# 9_-STM32F407_Controller.net
KiCad netlist of a schematic drawn in Altium Designer
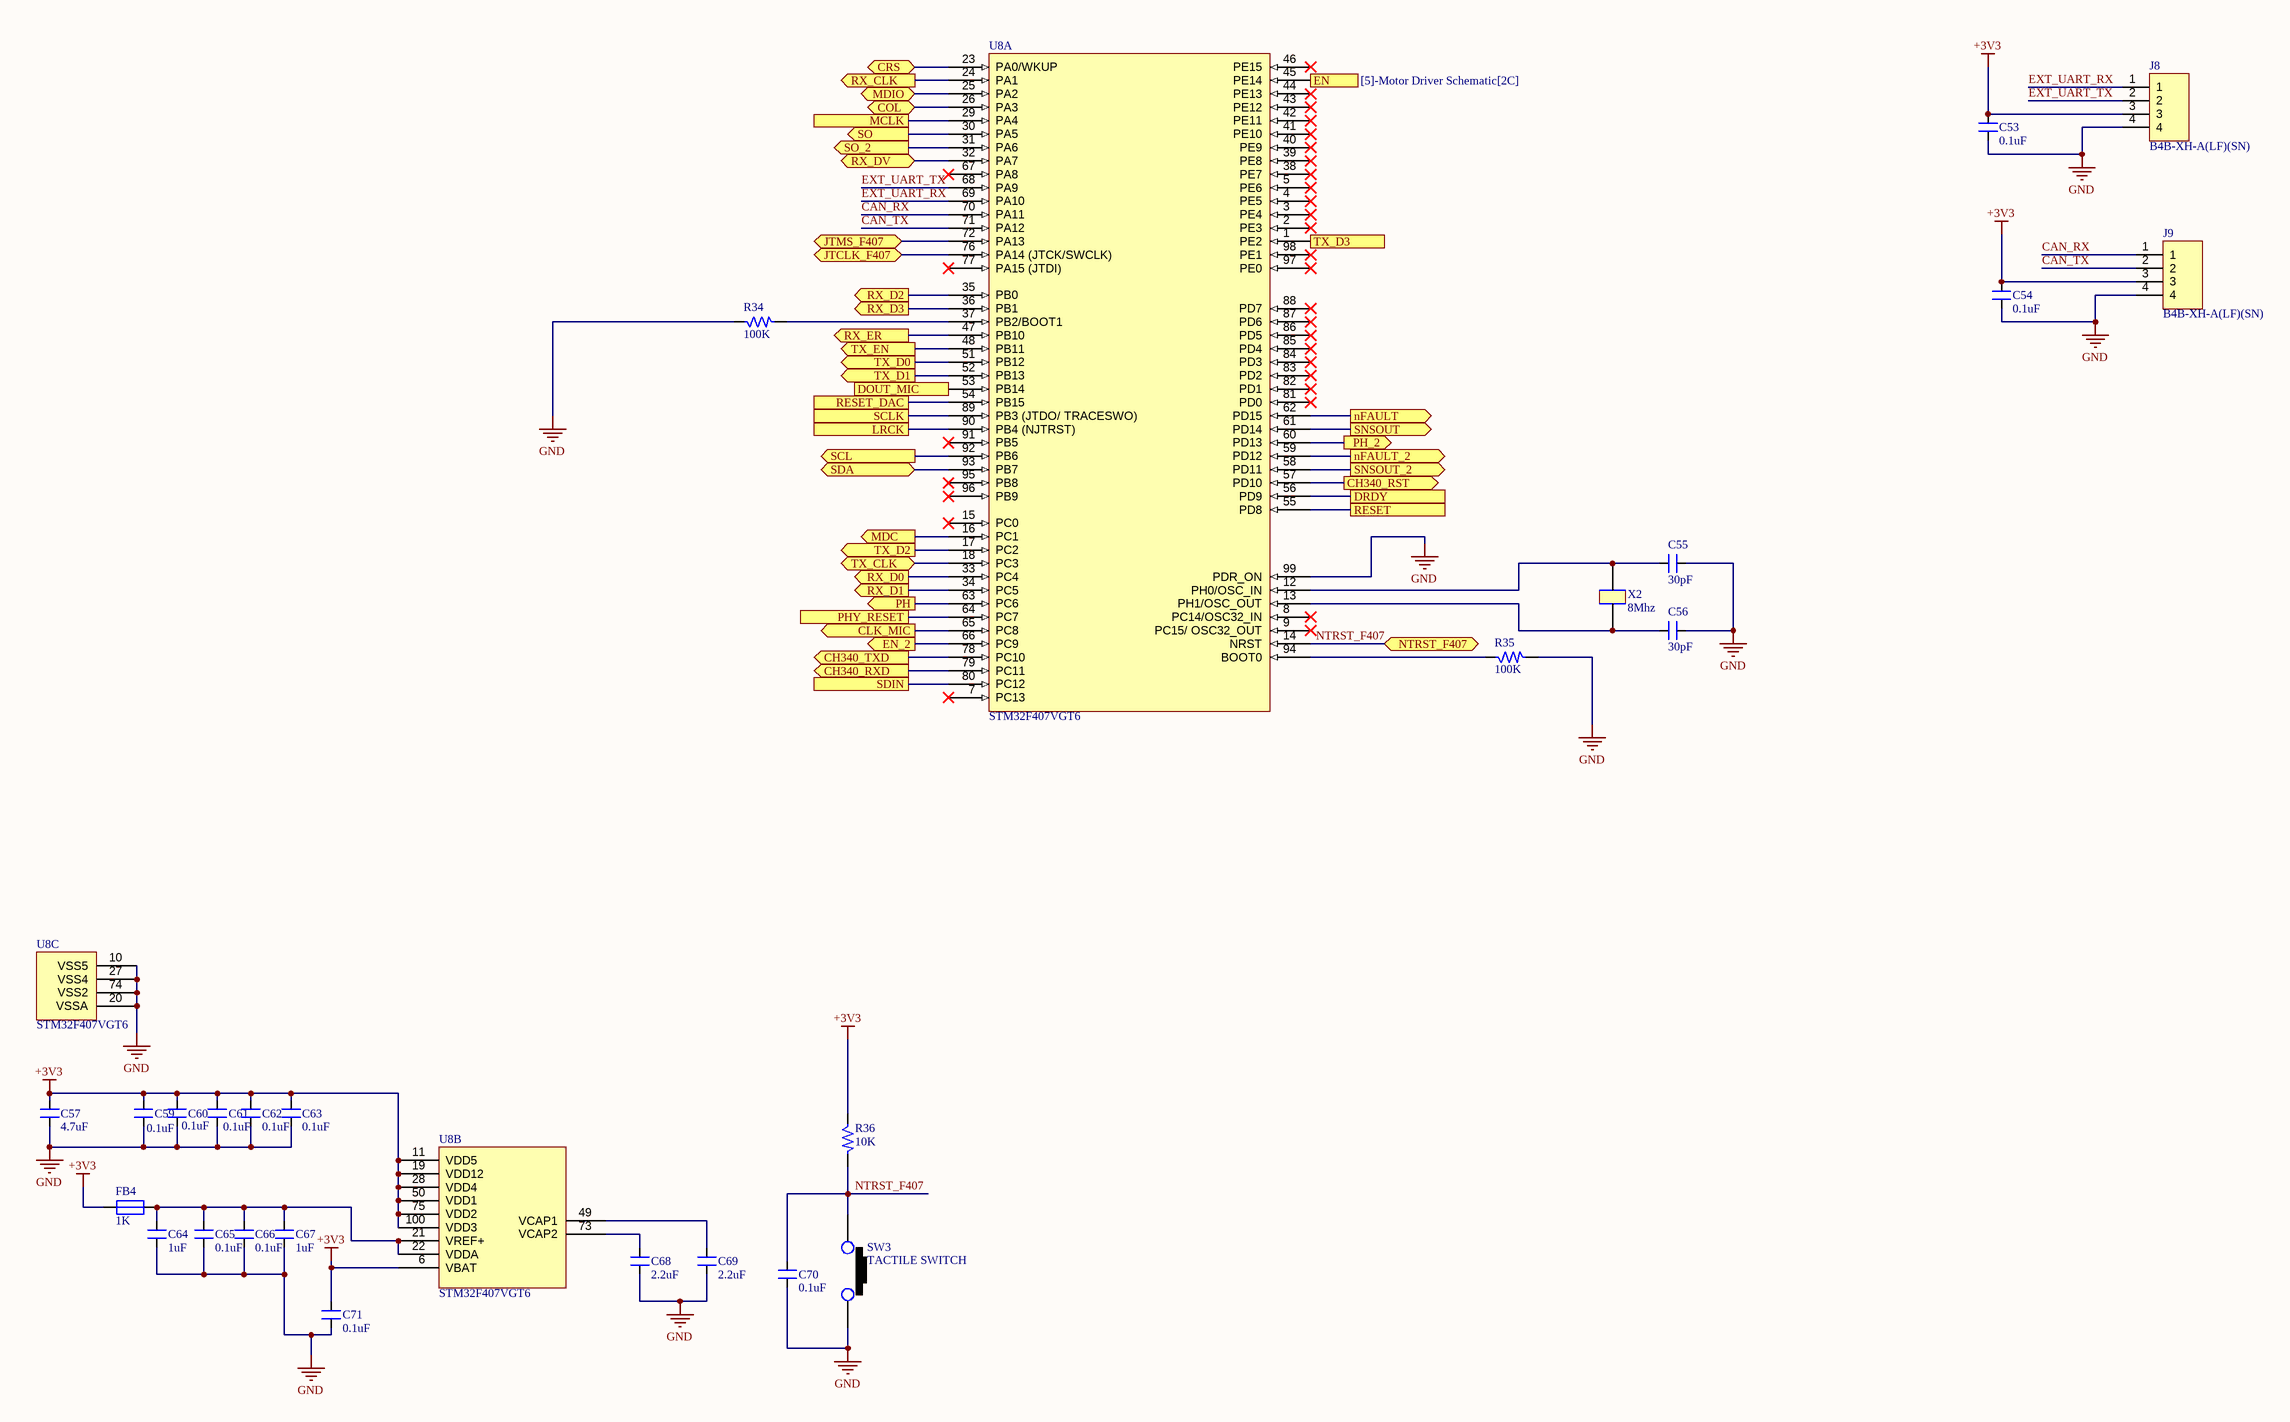
[diagram p0: [9]-STM32F407 Controller.SchDoc]

(export (version "E")
  (design (tool "Eeschema 10.0.6"))
  (components
    (comp (ref "C53")
      (value "0.1uF")
      (footprint "CAP_0805")
      (description "0.1µF ±10% 50V Ceramic Capacitor X7R 0805 (2012 Metric)")
      (fields
        (field (name "MANUFACTURER") "Samsung")
        (field (name "MANUFACTURER PART NUMBER") "CL21B104KBCNNNC")
      )
      (libsource (lib "ESTEEMPCBLIB") (part "CAP_0.1uF-50V-10%-0805"))
    )
    (comp (ref "C54")
      (value "0.1uF")
      (footprint "CAP_0805")
      (description "0.1µF ±10% 50V Ceramic Capacitor X7R 0805 (2012 Metric)")
      (fields
        (field (name "MANUFACTURER") "Samsung")
        (field (name "MANUFACTURER PART NUMBER") "CL21B104KBCNNNC")
      )
      (libsource (lib "ESTEEMPCBLIB") (part "CAP_0.1uF-50V-10%-0805"))
    )
    (comp (ref "C55")
      (value "30pF")
      (footprint "CAP_0805")
      (description "±10% 50V Ceramic Capacitor C0G, NP0 0805 (2012 Metric)")
      (fields
        (field (name "MANUFACTURER PART NUMBER") "C0805C300K5GAC7800")
        (field (name "MANUFACTURER") "KEMET")
      )
      (libsource (lib "ESTEEMPCBLIB") (part "CAP_30pF-50V-10%-0805"))
    )
    (comp (ref "C56")
      (value "30pF")
      (footprint "CAP_0805")
      (description "±10% 50V Ceramic Capacitor C0G, NP0 0805 (2012 Metric)")
      (fields
        (field (name "MANUFACTURER PART NUMBER") "C0805C300K5GAC7800")
        (field (name "MANUFACTURER") "KEMET")
      )
      (libsource (lib "ESTEEMPCBLIB") (part "CAP_30pF-50V-10%-0805"))
    )
    (comp (ref "C57")
      (value "4.7uF")
      (footprint "CAP_0805")
      (description "4.7µF ±10% 50V Ceramic Capacitor X5R 0805 (2012 Metric)")
      (fields
        (field (name "MANUFACTURER") "Yageo")
        (field (name "MANUFACTURER PART NUMBER") "GRM21BR61H475KE51L")
      )
      (libsource (lib "ESTEEMPCBLIB") (part "CAP_4.7uF-50V-10%-0805"))
    )
    (comp (ref "C59")
      (value "0.1uF")
      (footprint "CAP_0805")
      (description "0.1µF ±10% 50V Ceramic Capacitor X7R 0805 (2012 Metric)")
      (fields
        (field (name "MANUFACTURER") "Samsung")
        (field (name "MANUFACTURER PART NUMBER") "CL21B104KBCNNNC")
      )
      (libsource (lib "ESTEEMPCBLIB") (part "CAP_0.1uF-50V-10%-0805"))
    )
    (comp (ref "C60")
      (value "0.1uF")
      (footprint "CAP_0805")
      (description "0.1µF ±10% 50V Ceramic Capacitor X7R 0805 (2012 Metric)")
      (fields
        (field (name "MANUFACTURER") "Samsung")
        (field (name "MANUFACTURER PART NUMBER") "CL21B104KBCNNNC")
      )
      (libsource (lib "ESTEEMPCBLIB") (part "CAP_0.1uF-50V-10%-0805"))
    )
    (comp (ref "C61")
      (value "0.1uF")
      (footprint "CAP_0805")
      (description "0.1µF ±10% 50V Ceramic Capacitor X7R 0805 (2012 Metric)")
      (fields
        (field (name "MANUFACTURER") "Samsung")
        (field (name "MANUFACTURER PART NUMBER") "CL21B104KBCNNNC")
      )
      (libsource (lib "ESTEEMPCBLIB") (part "CAP_0.1uF-50V-10%-0805"))
    )
    (comp (ref "C62")
      (value "0.1uF")
      (footprint "CAP_0805")
      (description "0.1µF ±10% 50V Ceramic Capacitor X7R 0805 (2012 Metric)")
      (fields
        (field (name "MANUFACTURER") "Samsung")
        (field (name "MANUFACTURER PART NUMBER") "CL21B104KBCNNNC")
      )
      (libsource (lib "ESTEEMPCBLIB") (part "CAP_0.1uF-50V-10%-0805"))
    )
    (comp (ref "C63")
      (value "0.1uF")
      (footprint "CAP_0805")
      (description "0.1µF ±10% 50V Ceramic Capacitor X7R 0805 (2012 Metric)")
      (fields
        (field (name "MANUFACTURER") "Samsung")
        (field (name "MANUFACTURER PART NUMBER") "CL21B104KBCNNNC")
      )
      (libsource (lib "ESTEEMPCBLIB") (part "CAP_0.1uF-50V-10%-0805"))
    )
    (comp (ref "C64")
      (value "1uF")
      (footprint "CAP_0805")
      (description "1µF ±5% 50V Ceramic Capacitor X7R 0805 (2012 Metric)")
      (fields
        (field (name "MANUFACTURER") "Samsung")
        (field (name "MANUFACTURER PART NUMBER") "CC0805JKX7R9BB105")
      )
      (libsource (lib "ESTEEMPCBLIB") (part "CAP_1uF-50V-5%-0805"))
    )
    (comp (ref "C65")
      (value "0.1uF")
      (footprint "CAP_0805")
      (description "0.1µF ±10% 50V Ceramic Capacitor X7R 0805 (2012 Metric)")
      (fields
        (field (name "MANUFACTURER") "Samsung")
        (field (name "MANUFACTURER PART NUMBER") "CL21B104KBCNNNC")
      )
      (libsource (lib "ESTEEMPCBLIB") (part "CAP_0.1uF-50V-10%-0805"))
    )
    (comp (ref "C66")
      (value "0.1uF")
      (footprint "CAP_0805")
      (description "0.1µF ±10% 50V Ceramic Capacitor X7R 0805 (2012 Metric)")
      (fields
        (field (name "MANUFACTURER") "Samsung")
        (field (name "MANUFACTURER PART NUMBER") "CL21B104KBCNNNC")
      )
      (libsource (lib "ESTEEMPCBLIB") (part "CAP_0.1uF-50V-10%-0805"))
    )
    (comp (ref "C67")
      (value "1uF")
      (footprint "CAP_0805")
      (description "1µF ±5% 50V Ceramic Capacitor X7R 0805 (2012 Metric)")
      (fields
        (field (name "MANUFACTURER") "Samsung")
        (field (name "MANUFACTURER PART NUMBER") "CC0805JKX7R9BB105")
      )
      (libsource (lib "ESTEEMPCBLIB") (part "CAP_1uF-50V-5%-0805"))
    )
    (comp (ref "C68")
      (value "2.2uF")
      (footprint "CAP_0805")
      (description "2.2µF ±10% 25V Ceramic Capacitor X7R 0805 (2012 Metric)")
      (fields
        (field (name "MANUFACTURER") "KEMET")
        (field (name "MANUFACTURER PART NUMBER") "CL21B225KAFNFNE")
      )
      (libsource (lib "ESTEEMPCBLIB") (part "CAP_2.2uF-25V-10%-0805"))
    )
    (comp (ref "C69")
      (value "2.2uF")
      (footprint "CAP_0805")
      (description "2.2µF ±10% 25V Ceramic Capacitor X7R 0805 (2012 Metric)")
      (fields
        (field (name "MANUFACTURER") "KEMET")
        (field (name "MANUFACTURER PART NUMBER") "CL21B225KAFNFNE")
      )
      (libsource (lib "ESTEEMPCBLIB") (part "CAP_2.2uF-25V-10%-0805"))
    )
    (comp (ref "C70")
      (value "0.1uF")
      (footprint "CAP_0805")
      (description "0.1µF ±10% 50V Ceramic Capacitor X7R 0805 (2012 Metric)")
      (fields
        (field (name "MANUFACTURER") "Samsung")
        (field (name "MANUFACTURER PART NUMBER") "CL21B104KBCNNNC")
      )
      (libsource (lib "ESTEEMPCBLIB") (part "CAP_0.1uF-50V-10%-0805"))
    )
    (comp (ref "C71")
      (value "0.1uF")
      (footprint "CAP_0805")
      (description "0.1µF ±10% 50V Ceramic Capacitor X7R 0805 (2012 Metric)")
      (fields
        (field (name "MANUFACTURER") "Samsung")
        (field (name "MANUFACTURER PART NUMBER") "CL21B104KBCNNNC")
      )
      (libsource (lib "ESTEEMPCBLIB") (part "CAP_0.1uF-50V-10%-0805"))
    )
    (comp (ref "FB4")
      (value "1K")
      (footprint "IND_0805")
      (description "1 kOhms @ 100MHz 1 Power Line Ferrite Bead 0805 (2012 Metric) 1.6A")
      (fields
        (field (name "MANUFACTURER") "Laird")
        (field (name "MANUFACTURER PART NUMBER") "BLM21SP102SH1D")
      )
      (libsource (lib "ESTEEMPCBLIB") (part "FB_1K-100MHZ-1.6A-0805"))
    )
    (comp (ref "J8")
      (value "B4B-XH-A(LF)(SN)")
      (footprint "CON4_100_B4B-XH-A_TH_ST")
      (description "4 Pins, 1 Row 2.54mm Pitch, straight Connector, male")
      (fields (field (name "MANUFACTURER") "Wurth Electronics") (field (name "MATING PART NUMBER") "XHP-4"))
      (libsource (lib "ESTEEMPCBLIB") (part "CON-PLG_4X1-100-ST-TH"))
    )
    (comp (ref "J9")
      (value "B4B-XH-A(LF)(SN)")
      (footprint "CON4_100_B4B-XH-A_TH_ST")
      (description "4 Pins, 1 Row 2.54mm Pitch, straight Connector, male")
      (fields (field (name "MANUFACTURER") "Wurth Electronics") (field (name "MATING PART NUMBER") "XHP-4"))
      (libsource (lib "ESTEEMPCBLIB") (part "CON-PLG_4X1-100-ST-TH"))
    )
    (comp (ref "R34")
      (value "100K")
      (footprint "RES_0603")
      (description "100 kOhms ±1% 0.1W, 1/10W Chip Resistor 0603 (1608 Metric) Automotive AEC-Q200 Thick Film")
      (fields
        (field (name "MANUFACTURER") "Stackpole Electronics")
        (field (name "MANUFACTURER PART NUMBER") "RMCF0603FT100K")
      )
      (libsource (lib "ESTEEMPCBLIB") (part "RES_100K-0.1W-1%-0603"))
    )
    (comp (ref "R35")
      (value "100K")
      (footprint "RES_0603")
      (description "100 kOhms ±1% 0.1W, 1/10W Chip Resistor 0603 (1608 Metric) Automotive AEC-Q200 Thick Film")
      (fields
        (field (name "MANUFACTURER") "Stackpole Electronics")
        (field (name "MANUFACTURER PART NUMBER") "RMCF0603FT100K")
      )
      (libsource (lib "ESTEEMPCBLIB") (part "RES_100K-0.1W-1%-0603"))
    )
    (comp (ref "R36")
      (value "10K")
      (footprint "RES_0603")
      (description "10 kOhms ±1% 0.1W, 1/10W Chip Resistor 0603 (1608 Metric) Automotive AEC-Q200 Thick Film")
      (fields (field (name "MANUFACTURER") "Walsin") (field (name "MANUFACTURER PART NUMBER") "WR06X1002FTL"))
      (libsource (lib "ESTEEMPCBLIB") (part "RES_10K-0.1W-1%-0603"))
    )
    (comp (ref "SW3")
      (value "TACTILE SWITCH")
      (footprint "SW_342_SMD")
      (description "Tactile Switch SPST-NO Top Actuated Surface Mount")
      (fields
        (field (name "MANUFACTURER") "ITT C&K")
        (field (name "MANUFACTURER PART NUMBER") "RS-282G05A3-SMRT")
      )
      (libsource (lib "ESTEEMPCBLIB") (part "SW1_RS-282G05A3-SMRT-SMD"))
    )
    (comp (ref "U8")
      (value "STM32F407VGT6")
      (footprint "QFN100_19.6_669_58X10_SMD")
      (description "ARM® Cortex®-M4 STM32F4 Microcontroller IC 32-Bit 168MHz 1MB (1M x 8) FLASH 100-LQFP (14x14)")
      (fields (field (name "MANUFACTURER") "STMicroelectronics"))
      (libsource (lib "ESTEEMPCBLIB") (part "IC_STM32F407VGT6"))
    )
    (comp (ref "X2")
      (value "8Mhz")
      (footprint "XTAL_314_240X47_SMD")
      (description "8MHz ±30ppm Crystal 32pF 60 Ohms HC-49/US")
      (fields
        (field (name "MANUFACTURER") "Fox Electronics")
        (field (name "MANUFACTURER PART NUMBER") "ECS-80-32-5PX-TR")
      )
      (libsource (lib "ESTEEMPCBLIB") (part "XTAL_8MHZ-ECS-80-32-5PX-SMD"))
    )
  )
  (nets
    (net (code "1") (name "+3V3") (class "Default")
      (node (ref "C53") (pin "2") (pinfunction "2_2") (pintype "passive"))
      (node (ref "C54") (pin "2") (pinfunction "2_2") (pintype "passive"))
      (node (ref "C57") (pin "2") (pinfunction "2_2") (pintype "passive"))
      (node (ref "C59") (pin "2") (pinfunction "2_2") (pintype "passive"))
      (node (ref "C60") (pin "2") (pinfunction "2_2") (pintype "passive"))
      (node (ref "C61") (pin "2") (pinfunction "2_2") (pintype "passive"))
      (node (ref "C62") (pin "2") (pinfunction "2_2") (pintype "passive"))
      (node (ref "C63") (pin "2") (pinfunction "2_2") (pintype "passive"))
      (node (ref "C71") (pin "2") (pinfunction "2_2") (pintype "passive"))
      (node (ref "FB4") (pin "1") (pinfunction "1_1") (pintype "passive"))
      (node (ref "J8") (pin "3") (pinfunction "3_3") (pintype "passive"))
      (node (ref "J9") (pin "3") (pinfunction "3_3") (pintype "passive"))
      (node (ref "R36") (pin "1") (pinfunction "1_1") (pintype "passive"))
      (node (ref "U8") (pin "100") (pinfunction "VDD3_100") (pintype "passive"))
      (node (ref "U8") (pin "11") (pinfunction "VDD5_11") (pintype "passive"))
      (node (ref "U8") (pin "19") (pinfunction "VDD12_19") (pintype "passive"))
      (node (ref "U8") (pin "28") (pinfunction "VDD4_28") (pintype "passive"))
      (node (ref "U8") (pin "50") (pinfunction "VDD1_50") (pintype "passive"))
      (node (ref "U8") (pin "6") (pinfunction "VBAT_6") (pintype "passive"))
      (node (ref "U8") (pin "75") (pinfunction "VDD2_75") (pintype "passive"))
    )
    (net (code "2") (name "/CAN_RX") (class "Default")
      (node (ref "J9") (pin "1") (pinfunction "1_1") (pintype "passive"))
      (node (ref "U8") (pin "70") (pinfunction "PA11_70") (pintype "input"))
    )
    (net (code "3") (name "/CAN_TX") (class "Default")
      (node (ref "J9") (pin "2") (pinfunction "2_2") (pintype "passive"))
      (node (ref "U8") (pin "71") (pinfunction "PA12_71") (pintype "input"))
    )
    (net (code "4") (name "/CH340_RST") (class "Default")
      (node (ref "U8") (pin "57") (pinfunction "PD10_57") (pintype "input"))
    )
    (net (code "5") (name "/CH340_RXD") (class "Default")
      (node (ref "U8") (pin "79") (pinfunction "PC11_79") (pintype "input"))
    )
    (net (code "6") (name "/CH340_TXD") (class "Default")
      (node (ref "U8") (pin "78") (pinfunction "PC10_78") (pintype "input"))
    )
    (net (code "7") (name "/CLK_MIC") (class "Default")
      (node (ref "U8") (pin "65") (pinfunction "PC8_65") (pintype "input"))
    )
    (net (code "8") (name "/COL") (class "Default")
      (node (ref "U8") (pin "26") (pinfunction "PA3_26") (pintype "input"))
    )
    (net (code "9") (name "/CRS") (class "Default")
      (node (ref "U8") (pin "23") (pinfunction "PA0/WKUP_23") (pintype "input"))
    )
    (net (code "10") (name "/DOUT_MIC") (class "Default")
      (node (ref "U8") (pin "53") (pinfunction "PB14_53") (pintype "input"))
    )
    (net (code "11") (name "/DRDY") (class "Default")
      (node (ref "U8") (pin "56") (pinfunction "PD9_56") (pintype "input"))
    )
    (net (code "12") (name "/EN") (class "Default")
      (node (ref "U8") (pin "45") (pinfunction "PE14_45") (pintype "input"))
    )
    (net (code "13") (name "/EN_2") (class "Default")
      (node (ref "U8") (pin "66") (pinfunction "PC9_66") (pintype "input"))
    )
    (net (code "14") (name "/EXT_UART_RX") (class "Default")
      (node (ref "J8") (pin "1") (pinfunction "1_1") (pintype "passive"))
      (node (ref "U8") (pin "69") (pinfunction "PA10_69") (pintype "input"))
    )
    (net (code "15") (name "/EXT_UART_TX") (class "Default")
      (node (ref "J8") (pin "2") (pinfunction "2_2") (pintype "passive"))
      (node (ref "U8") (pin "68") (pinfunction "PA9_68") (pintype "input"))
    )
    (net (code "16") (name "/JTCLK_F407") (class "Default")
      (node (ref "U8") (pin "76") (pinfunction "PA14_(JTCK/SWCLK)_76") (pintype "input"))
    )
    (net (code "17") (name "/JTMS_F407") (class "Default")
      (node (ref "U8") (pin "72") (pinfunction "PA13_72") (pintype "input"))
    )
    (net (code "18") (name "/LRCK") (class "Default")
      (node (ref "U8") (pin "90") (pinfunction "PB4_(NJTRST)_90") (pintype "input"))
    )
    (net (code "19") (name "/MCLK") (class "Default")
      (node (ref "U8") (pin "29") (pinfunction "PA4_29") (pintype "input"))
    )
    (net (code "20") (name "/MDC") (class "Default")
      (node (ref "U8") (pin "16") (pinfunction "PC1_16") (pintype "input"))
    )
    (net (code "21") (name "/MDIO") (class "Default")
      (node (ref "U8") (pin "25") (pinfunction "PA2_25") (pintype "input"))
    )
    (net (code "22") (name "/NTRST_F407") (class "Default")
      (node (ref "C70") (pin "2") (pinfunction "2_2") (pintype "passive"))
      (node (ref "R36") (pin "2") (pinfunction "2_2") (pintype "passive"))
      (node (ref "SW3") (pin "1") (pinfunction "1_1") (pintype "passive"))
      (node (ref "U8") (pin "14") (pinfunction "NRST_14") (pintype "input"))
    )
    (net (code "23") (name "/PH") (class "Default")
      (node (ref "U8") (pin "63") (pinfunction "PC6_63") (pintype "input"))
    )
    (net (code "24") (name "/PHY_RESET") (class "Default")
      (node (ref "U8") (pin "64") (pinfunction "PC7_64") (pintype "input"))
    )
    (net (code "25") (name "/PH_2") (class "Default")
      (node (ref "U8") (pin "60") (pinfunction "PD13_60") (pintype "input"))
    )
    (net (code "26") (name "/RESET") (class "Default")
      (node (ref "U8") (pin "55") (pinfunction "PD8_55") (pintype "input"))
    )
    (net (code "27") (name "/RESET_DAC") (class "Default")
      (node (ref "U8") (pin "54") (pinfunction "PB15_54") (pintype "input"))
    )
    (net (code "28") (name "/RX_CLK") (class "Default")
      (node (ref "U8") (pin "24") (pinfunction "PA1_24") (pintype "input"))
    )
    (net (code "29") (name "/RX_D0") (class "Default")
      (node (ref "U8") (pin "33") (pinfunction "PC4_33") (pintype "input"))
    )
    (net (code "30") (name "/RX_D1") (class "Default")
      (node (ref "U8") (pin "34") (pinfunction "PC5_34") (pintype "input"))
    )
    (net (code "31") (name "/RX_D2") (class "Default")
      (node (ref "U8") (pin "35") (pinfunction "PB0_35") (pintype "input"))
    )
    (net (code "32") (name "/RX_D3") (class "Default")
      (node (ref "U8") (pin "36") (pinfunction "PB1_36") (pintype "input"))
    )
    (net (code "33") (name "/RX_DV") (class "Default")
      (node (ref "U8") (pin "32") (pinfunction "PA7_32") (pintype "input"))
    )
    (net (code "34") (name "/RX_ER") (class "Default")
      (node (ref "U8") (pin "47") (pinfunction "PB10_47") (pintype "input"))
    )
    (net (code "35") (name "/SCL") (class "Default")
      (node (ref "U8") (pin "92") (pinfunction "PB6_92") (pintype "input"))
    )
    (net (code "36") (name "/SCLK") (class "Default")
      (node (ref "U8") (pin "89") (pinfunction "PB3_(JTDO/_TRACESWO)_89") (pintype "input"))
    )
    (net (code "37") (name "/SDA") (class "Default")
      (node (ref "U8") (pin "93") (pinfunction "PB7_93") (pintype "input"))
    )
    (net (code "38") (name "/SDIN") (class "Default")
      (node (ref "U8") (pin "80") (pinfunction "PC12_80") (pintype "input"))
    )
    (net (code "39") (name "/SNSOUT") (class "Default")
      (node (ref "U8") (pin "61") (pinfunction "PD14_61") (pintype "input"))
    )
    (net (code "40") (name "/SNSOUT_2") (class "Default")
      (node (ref "U8") (pin "58") (pinfunction "PD11_58") (pintype "input"))
    )
    (net (code "41") (name "/SO") (class "Default")
      (node (ref "U8") (pin "30") (pinfunction "PA5_30") (pintype "input"))
    )
    (net (code "42") (name "/SO_2") (class "Default")
      (node (ref "U8") (pin "31") (pinfunction "PA6_31") (pintype "input"))
    )
    (net (code "43") (name "/TX_CLK") (class "Default")
      (node (ref "U8") (pin "18") (pinfunction "PC3_18") (pintype "input"))
    )
    (net (code "44") (name "/TX_D0") (class "Default")
      (node (ref "U8") (pin "51") (pinfunction "PB12_51") (pintype "input"))
    )
    (net (code "45") (name "/TX_D1") (class "Default")
      (node (ref "U8") (pin "52") (pinfunction "PB13_52") (pintype "input"))
    )
    (net (code "46") (name "/TX_D2") (class "Default")
      (node (ref "U8") (pin "17") (pinfunction "PC2_17") (pintype "input"))
    )
    (net (code "47") (name "/TX_D3") (class "Default")
      (node (ref "U8") (pin "1") (pinfunction "PE2_1") (pintype "input"))
    )
    (net (code "48") (name "/TX_EN") (class "Default")
      (node (ref "U8") (pin "48") (pinfunction "PB11_48") (pintype "input"))
    )
    (net (code "49") (name "/nFAULT") (class "Default")
      (node (ref "U8") (pin "62") (pinfunction "PD15_62") (pintype "input"))
    )
    (net (code "50") (name "/nFAULT_2") (class "Default")
      (node (ref "U8") (pin "59") (pinfunction "PD12_59") (pintype "input"))
    )
    (net (code "51") (name "GND") (class "Default")
      (node (ref "C53") (pin "1") (pinfunction "1_1") (pintype "passive"))
      (node (ref "C54") (pin "1") (pinfunction "1_1") (pintype "passive"))
      (node (ref "C55") (pin "2") (pinfunction "2_2") (pintype "passive"))
      (node (ref "C56") (pin "2") (pinfunction "2_2") (pintype "passive"))
      (node (ref "C57") (pin "1") (pinfunction "1_1") (pintype "passive"))
      (node (ref "C59") (pin "1") (pinfunction "1_1") (pintype "passive"))
      (node (ref "C60") (pin "1") (pinfunction "1_1") (pintype "passive"))
      (node (ref "C61") (pin "1") (pinfunction "1_1") (pintype "passive"))
      (node (ref "C62") (pin "1") (pinfunction "1_1") (pintype "passive"))
      (node (ref "C63") (pin "1") (pinfunction "1_1") (pintype "passive"))
      (node (ref "C64") (pin "1") (pinfunction "1_1") (pintype "passive"))
      (node (ref "C65") (pin "1") (pinfunction "1_1") (pintype "passive"))
      (node (ref "C66") (pin "1") (pinfunction "1_1") (pintype "passive"))
      (node (ref "C67") (pin "1") (pinfunction "1_1") (pintype "passive"))
      (node (ref "C68") (pin "1") (pinfunction "1_1") (pintype "passive"))
      (node (ref "C69") (pin "1") (pinfunction "1_1") (pintype "passive"))
      (node (ref "C70") (pin "1") (pinfunction "1_1") (pintype "passive"))
      (node (ref "C71") (pin "1") (pinfunction "1_1") (pintype "passive"))
      (node (ref "J8") (pin "4") (pinfunction "4_4") (pintype "passive"))
      (node (ref "J9") (pin "4") (pinfunction "4_4") (pintype "passive"))
      (node (ref "R34") (pin "1") (pinfunction "1_1") (pintype "passive"))
      (node (ref "R35") (pin "2") (pinfunction "2_2") (pintype "passive"))
      (node (ref "SW3") (pin "2") (pinfunction "2_2") (pintype "passive"))
      (node (ref "U8") (pin "10") (pinfunction "VSS5_10") (pintype "passive"))
      (node (ref "U8") (pin "20") (pinfunction "VSSA_20") (pintype "passive"))
      (node (ref "U8") (pin "27") (pinfunction "VSS4_27") (pintype "passive"))
      (node (ref "U8") (pin "74") (pinfunction "VSS2_74") (pintype "passive"))
      (node (ref "U8") (pin "99") (pinfunction "PDR_ON_99") (pintype "input"))
    )
    (net (code "52") (name "Net-(U8A-BOOT0)") (class "Default")
      (node (ref "R35") (pin "1") (pinfunction "1_1") (pintype "passive"))
      (node (ref "U8") (pin "94") (pinfunction "BOOT0_94") (pintype "input"))
    )
    (net (code "53") (name "Net-(U8A-PB2{slash}BOOT1)") (class "Default")
      (node (ref "R34") (pin "2") (pinfunction "2_2") (pintype "passive"))
      (node (ref "U8") (pin "37") (pinfunction "PB2/BOOT1_37") (pintype "input"))
    )
    (net (code "54") (name "Net-(U8A-PH0{slash}OSC_IN)") (class "Default")
      (node (ref "C55") (pin "1") (pinfunction "1_1") (pintype "passive"))
      (node (ref "U8") (pin "12") (pinfunction "PH0/OSC_IN_12") (pintype "input"))
      (node (ref "X2") (pin "2") (pinfunction "2_2") (pintype "passive"))
    )
    (net (code "55") (name "Net-(U8A-PH1{slash}OSC_OUT)") (class "Default")
      (node (ref "C56") (pin "1") (pinfunction "1_1") (pintype "passive"))
      (node (ref "U8") (pin "13") (pinfunction "PH1/OSC_OUT_13") (pintype "input"))
      (node (ref "X2") (pin "1") (pinfunction "1_1") (pintype "passive"))
    )
    (net (code "56") (name "Net-(U8B-VCAP1)") (class "Default")
      (node (ref "C69") (pin "2") (pinfunction "2_2") (pintype "passive"))
      (node (ref "U8") (pin "49") (pinfunction "VCAP1_49") (pintype "passive"))
    )
    (net (code "57") (name "Net-(U8B-VCAP2)") (class "Default")
      (node (ref "C68") (pin "2") (pinfunction "2_2") (pintype "passive"))
      (node (ref "U8") (pin "73") (pinfunction "VCAP2_73") (pintype "passive"))
    )
    (net (code "58") (name "Net-(U8B-VDDA)") (class "Default")
      (node (ref "C64") (pin "2") (pinfunction "2_2") (pintype "passive"))
      (node (ref "C65") (pin "2") (pinfunction "2_2") (pintype "passive"))
      (node (ref "C66") (pin "2") (pinfunction "2_2") (pintype "passive"))
      (node (ref "C67") (pin "2") (pinfunction "2_2") (pintype "passive"))
      (node (ref "FB4") (pin "2") (pinfunction "2_2") (pintype "passive"))
      (node (ref "U8") (pin "21") (pinfunction "VREF+_21") (pintype "passive"))
      (node (ref "U8") (pin "22") (pinfunction "VDDA_22") (pintype "passive"))
    )
    (net (code "59") (name "unconnected-(U8A-PA8-Pad67)") (class "Default")
      (node (ref "U8") (pin "67") (pinfunction "PA8_67") (pintype "input+no_connect"))
    )
    (net (code "60") (name "unconnected-(U8A-PA15_(JTDI)-Pad77)") (class "Default")
      (node (ref "U8") (pin "77") (pinfunction "PA15_(JTDI)_77") (pintype "input+no_connect"))
    )
    (net (code "61") (name "unconnected-(U8A-PB5-Pad91)") (class "Default")
      (node (ref "U8") (pin "91") (pinfunction "PB5_91") (pintype "input+no_connect"))
    )
    (net (code "62") (name "unconnected-(U8A-PB8-Pad95)") (class "Default")
      (node (ref "U8") (pin "95") (pinfunction "PB8_95") (pintype "input+no_connect"))
    )
    (net (code "63") (name "unconnected-(U8A-PB9-Pad96)") (class "Default")
      (node (ref "U8") (pin "96") (pinfunction "PB9_96") (pintype "input+no_connect"))
    )
    (net (code "64") (name "unconnected-(U8A-PC0-Pad15)") (class "Default")
      (node (ref "U8") (pin "15") (pinfunction "PC0_15") (pintype "input+no_connect"))
    )
    (net (code "65") (name "unconnected-(U8A-PC13-Pad7)") (class "Default")
      (node (ref "U8") (pin "7") (pinfunction "PC13_7") (pintype "input+no_connect"))
    )
    (net (code "66") (name "unconnected-(U8A-PC14{slash}OSC32_IN-Pad8)") (class "Default")
      (node (ref "U8") (pin "8") (pinfunction "PC14/OSC32_IN_8") (pintype "input+no_connect"))
    )
    (net (code "67") (name "unconnected-(U8A-PC15{slash}_OSC32_OUT-Pad9)") (class "Default")
      (node (ref "U8") (pin "9") (pinfunction "PC15/_OSC32_OUT_9") (pintype "input+no_connect"))
    )
    (net (code "68") (name "unconnected-(U8A-PD0-Pad81)") (class "Default")
      (node (ref "U8") (pin "81") (pinfunction "PD0_81") (pintype "input+no_connect"))
    )
    (net (code "69") (name "unconnected-(U8A-PD1-Pad82)") (class "Default")
      (node (ref "U8") (pin "82") (pinfunction "PD1_82") (pintype "input+no_connect"))
    )
    (net (code "70") (name "unconnected-(U8A-PD2-Pad83)") (class "Default")
      (node (ref "U8") (pin "83") (pinfunction "PD2_83") (pintype "input+no_connect"))
    )
    (net (code "71") (name "unconnected-(U8A-PD3-Pad84)") (class "Default")
      (node (ref "U8") (pin "84") (pinfunction "PD3_84") (pintype "input+no_connect"))
    )
    (net (code "72") (name "unconnected-(U8A-PD4-Pad85)") (class "Default")
      (node (ref "U8") (pin "85") (pinfunction "PD4_85") (pintype "input+no_connect"))
    )
    (net (code "73") (name "unconnected-(U8A-PD5-Pad86)") (class "Default")
      (node (ref "U8") (pin "86") (pinfunction "PD5_86") (pintype "input+no_connect"))
    )
    (net (code "74") (name "unconnected-(U8A-PD6-Pad87)") (class "Default")
      (node (ref "U8") (pin "87") (pinfunction "PD6_87") (pintype "input+no_connect"))
    )
    (net (code "75") (name "unconnected-(U8A-PD7-Pad88)") (class "Default")
      (node (ref "U8") (pin "88") (pinfunction "PD7_88") (pintype "input+no_connect"))
    )
    (net (code "76") (name "unconnected-(U8A-PE0-Pad97)") (class "Default")
      (node (ref "U8") (pin "97") (pinfunction "PE0_97") (pintype "input+no_connect"))
    )
    (net (code "77") (name "unconnected-(U8A-PE1-Pad98)") (class "Default")
      (node (ref "U8") (pin "98") (pinfunction "PE1_98") (pintype "input+no_connect"))
    )
    (net (code "78") (name "unconnected-(U8A-PE3-Pad2)") (class "Default")
      (node (ref "U8") (pin "2") (pinfunction "PE3_2") (pintype "input+no_connect"))
    )
    (net (code "79") (name "unconnected-(U8A-PE4-Pad3)") (class "Default")
      (node (ref "U8") (pin "3") (pinfunction "PE4_3") (pintype "input+no_connect"))
    )
    (net (code "80") (name "unconnected-(U8A-PE5-Pad4)") (class "Default")
      (node (ref "U8") (pin "4") (pinfunction "PE5_4") (pintype "input+no_connect"))
    )
    (net (code "81") (name "unconnected-(U8A-PE6-Pad5)") (class "Default")
      (node (ref "U8") (pin "5") (pinfunction "PE6_5") (pintype "input+no_connect"))
    )
    (net (code "82") (name "unconnected-(U8A-PE7-Pad38)") (class "Default")
      (node (ref "U8") (pin "38") (pinfunction "PE7_38") (pintype "input+no_connect"))
    )
    (net (code "83") (name "unconnected-(U8A-PE8-Pad39)") (class "Default")
      (node (ref "U8") (pin "39") (pinfunction "PE8_39") (pintype "input+no_connect"))
    )
    (net (code "84") (name "unconnected-(U8A-PE9-Pad40)") (class "Default")
      (node (ref "U8") (pin "40") (pinfunction "PE9_40") (pintype "input+no_connect"))
    )
    (net (code "85") (name "unconnected-(U8A-PE10-Pad41)") (class "Default")
      (node (ref "U8") (pin "41") (pinfunction "PE10_41") (pintype "input+no_connect"))
    )
    (net (code "86") (name "unconnected-(U8A-PE11-Pad42)") (class "Default")
      (node (ref "U8") (pin "42") (pinfunction "PE11_42") (pintype "input+no_connect"))
    )
    (net (code "87") (name "unconnected-(U8A-PE12-Pad43)") (class "Default")
      (node (ref "U8") (pin "43") (pinfunction "PE12_43") (pintype "input+no_connect"))
    )
    (net (code "88") (name "unconnected-(U8A-PE13-Pad44)") (class "Default")
      (node (ref "U8") (pin "44") (pinfunction "PE13_44") (pintype "input+no_connect"))
    )
    (net (code "89") (name "unconnected-(U8A-PE15-Pad46)") (class "Default")
      (node (ref "U8") (pin "46") (pinfunction "PE15_46") (pintype "input+no_connect"))
    )
  )
)
